# timmy.net
KiCad netlist of a schematic drawn in EAGLE
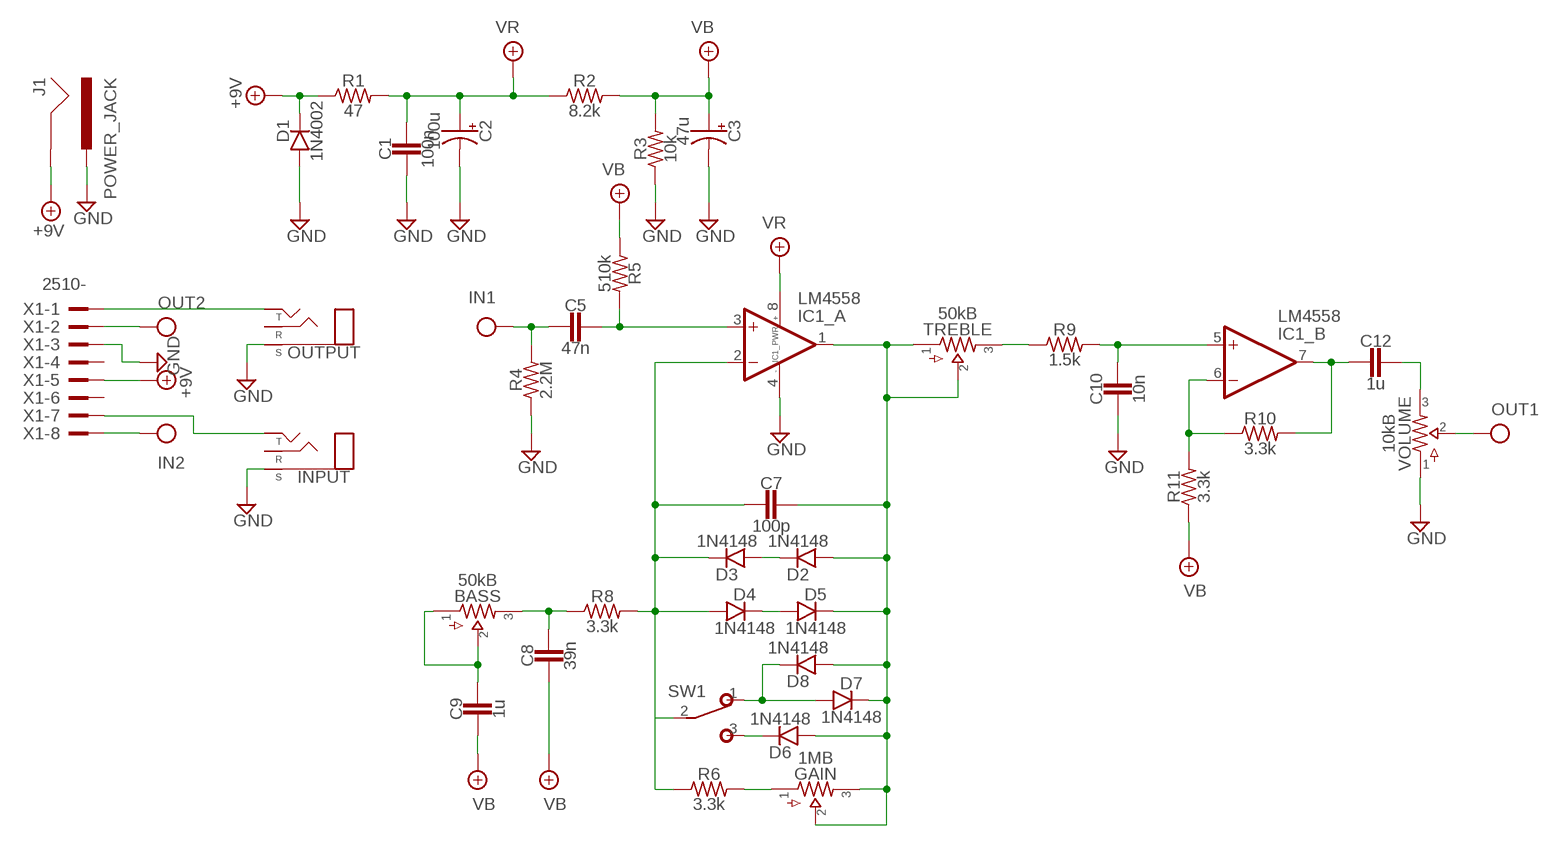
[diagram p0: schematic, sheet 1]

(export (version "E")
  (design (tool "Eeschema 10.0.6"))
  (components
    (comp (ref "BASS")
      (value "50kB")
      (footprint "eagle-import:16MM")
      (libsource (lib "eagle-import") (part "POTS16MM"))
    )
    (comp (ref "C1")
      (value "100n")
      (footprint "eagle-import:050X030_025_2")
      (libsource (lib "eagle-import") (part "CER/FILM2"))
    )
    (comp (ref "C2")
      (value "100u")
      (footprint "eagle-import:050_020")
      (libsource (lib "eagle-import") (part "0500"))
    )
    (comp (ref "C3")
      (value "47u")
      (footprint "eagle-import:050_020")
      (libsource (lib "eagle-import") (part "0500"))
    )
    (comp (ref "C5")
      (value "47n")
      (footprint "eagle-import:BOX_SMALL")
      (libsource (lib "eagle-import") (part "CER/FILMBOX.1"))
    )
    (comp (ref "C7")
      (value "100p")
      (footprint "eagle-import:050X030_025_2")
      (libsource (lib "eagle-import") (part "CER/FILM2"))
    )
    (comp (ref "C8")
      (value "39n")
      (footprint "eagle-import:BOX_SMALL")
      (libsource (lib "eagle-import") (part "CER/FILMBOX.1"))
    )
    (comp (ref "C9")
      (value "1u")
      (footprint "eagle-import:BOX_BIG")
      (libsource (lib "eagle-import") (part "CER/FILMBOX.3"))
    )
    (comp (ref "C10")
      (value "10n")
      (footprint "eagle-import:BOX_SMALL")
      (libsource (lib "eagle-import") (part "CER/FILMBOX.1"))
    )
    (comp (ref "C12")
      (value "1u")
      (footprint "eagle-import:BOX_BIG")
      (libsource (lib "eagle-import") (part "CER/FILMBOX.3"))
    )
    (comp (ref "D1")
      (value "1N4002")
      (footprint "eagle-import:DO41-2")
      (libsource (lib "eagle-import") (part "DO41.2"))
    )
    (comp (ref "D2")
      (value "1N4148")
      (footprint "eagle-import:DO35-2")
      (libsource (lib "eagle-import") (part "DO35.2"))
    )
    (comp (ref "D3")
      (value "1N4148")
      (footprint "eagle-import:DO35-2")
      (libsource (lib "eagle-import") (part "DO35.2"))
    )
    (comp (ref "D4")
      (value "1N4148")
      (footprint "eagle-import:DO35-2")
      (libsource (lib "eagle-import") (part "DO35.2"))
    )
    (comp (ref "D5")
      (value "1N4148")
      (footprint "eagle-import:DO35-2")
      (libsource (lib "eagle-import") (part "DO35.2"))
    )
    (comp (ref "D6")
      (value "1N4148")
      (footprint "eagle-import:DO35-2")
      (libsource (lib "eagle-import") (part "DO35.2"))
    )
    (comp (ref "D7")
      (value "1N4148")
      (footprint "eagle-import:DO35-2")
      (libsource (lib "eagle-import") (part "DO35.2"))
    )
    (comp (ref "D8")
      (value "1N4148")
      (footprint "eagle-import:DO35-2")
      (libsource (lib "eagle-import") (part "DO35.2"))
    )
    (comp (ref "GAIN")
      (value "1MB")
      (footprint "eagle-import:16MM")
      (libsource (lib "eagle-import") (part "POTS16MM"))
    )
    (comp (ref "IC1")
      (value "LM4558")
      (footprint "eagle-import:DIL08")
      (libsource (lib "eagle-import") (part "DUALTH"))
    )
    (comp (ref "INPUT")
      (value "STEREONMJ")
      (footprint "eagle-import:NMJ6HCD2")
      (libsource (lib "eagle-import") (part "STEREONMJ"))
    )
    (comp (ref "J1")
      (value "POWER_JACK")
      (footprint "eagle-import:POWER_JACK_PTH")
      (libsource (lib "eagle-import") (part "POWER_JACK"))
    )
    (comp (ref "OUTPUT")
      (value "STEREONMJ")
      (footprint "eagle-import:NMJ6HCD2")
      (libsource (lib "eagle-import") (part "STEREONMJ"))
    )
    (comp (ref "R1")
      (value "47")
      (footprint "eagle-import:R0207_3")
      (libsource (lib "eagle-import") (part "R_.3B"))
    )
    (comp (ref "R2")
      (value "8.2k")
      (footprint "eagle-import:R0207_3")
      (libsource (lib "eagle-import") (part "R_.3B"))
    )
    (comp (ref "R3")
      (value "10k")
      (footprint "eagle-import:R0207_3")
      (libsource (lib "eagle-import") (part "R_.3B"))
    )
    (comp (ref "R4")
      (value "2.2M")
      (footprint "eagle-import:R0207_3")
      (libsource (lib "eagle-import") (part "R_.3B"))
    )
    (comp (ref "R5")
      (value "510k")
      (footprint "eagle-import:R0207_3")
      (libsource (lib "eagle-import") (part "R_.3B"))
    )
    (comp (ref "R6")
      (value "3.3k")
      (footprint "eagle-import:R0207_3")
      (libsource (lib "eagle-import") (part "R_.3B"))
    )
    (comp (ref "R8")
      (value "3.3k")
      (footprint "eagle-import:R0207_3")
      (libsource (lib "eagle-import") (part "R_.3B"))
    )
    (comp (ref "R9")
      (value "1.5k")
      (footprint "eagle-import:R0207_3")
      (libsource (lib "eagle-import") (part "R_.3B"))
    )
    (comp (ref "R10")
      (value "3.3k")
      (footprint "eagle-import:R0207_3")
      (libsource (lib "eagle-import") (part "R_.3B"))
    )
    (comp (ref "R11")
      (value "3.3k")
      (footprint "eagle-import:R0207_3")
      (libsource (lib "eagle-import") (part "R_.3B"))
    )
    (comp (ref "SW1")
      (value "SPDT")
      (footprint "eagle-import:M9040P")
      (libsource (lib "eagle-import") (part "SPDT"))
    )
    (comp (ref "TREBLE")
      (value "50kB")
      (footprint "eagle-import:16MM")
      (libsource (lib "eagle-import") (part "POTS16MM"))
    )
    (comp (ref "VOLUME")
      (value "10kB")
      (footprint "eagle-import:16MM")
      (libsource (lib "eagle-import") (part "POTS16MM"))
    )
    (comp (ref "X1")
      (value "2510-")
      (footprint "eagle-import:PAK100_2500-10")
      (fields (field (name "MF") "3M") (field (name "MPN") "2510-6002UB"))
      (libsource (lib "eagle-import") (part "2510-"))
    )
  )
  (nets
    (net (code "1") (name "+9V") (class "Default")
      (node (ref "D1") (pin "C") (pinfunction "C_C") (pintype "passive"))
      (node (ref "J1") (pin "GND") (pinfunction "GND_GND") (pintype "bidirectional"))
      (node (ref "R1") (pin "1") (pinfunction "1_1") (pintype "passive"))
      (node (ref "X1") (pin "5") (pinfunction "KL_5") (pintype "passive"))
    )
    (net (code "2") (name "GND") (class "Default")
      (node (ref "C1") (pin "2") (pinfunction "2_2") (pintype "passive"))
      (node (ref "C10") (pin "2") (pinfunction "2_2") (pintype "passive"))
      (node (ref "C2") (pin "-") (pinfunction "-_-") (pintype "passive"))
      (node (ref "C3") (pin "-") (pinfunction "-_-") (pintype "passive"))
      (node (ref "D1") (pin "A") (pinfunction "A_A") (pintype "passive"))
      (node (ref "IC1") (pin "4") (pinfunction "V-_4") (pintype "power_in"))
      (node (ref "INPUT") (pin "S") (pinfunction "S_S") (pintype "passive"))
      (node (ref "J1") (pin "PWR") (pinfunction "PWR_PWR") (pintype "bidirectional"))
      (node (ref "OUTPUT") (pin "S") (pinfunction "S_S") (pintype "passive"))
      (node (ref "R3") (pin "1") (pinfunction "1_1") (pintype "passive"))
      (node (ref "R4") (pin "1") (pinfunction "1_1") (pintype "passive"))
      (node (ref "VOLUME") (pin "1") (pinfunction "1_1") (pintype "passive"))
      (node (ref "X1") (pin "3") (pinfunction "KL_3") (pintype "passive"))
    )
    (net (code "3") (name "IN") (class "Default")
      (node (ref "C5") (pin "2") (pinfunction "2_2") (pintype "passive"))
      (node (ref "R4") (pin "2") (pinfunction "2_2") (pintype "passive"))
      (node (ref "X1") (pin "8") (pinfunction "KL_8") (pintype "passive"))
    )
    (net (code "4") (name "Net-(BASS-Pad1)") (class "Default")
      (node (ref "BASS") (pin "1") (pinfunction "1_1") (pintype "passive"))
      (node (ref "BASS") (pin "2") (pinfunction "2_2") (pintype "passive"))
      (node (ref "C9") (pin "1") (pinfunction "1_1") (pintype "passive"))
    )
    (net (code "5") (name "Net-(BASS-Pad3)") (class "Default")
      (node (ref "BASS") (pin "3") (pinfunction "3_3") (pintype "passive"))
      (node (ref "C8") (pin "1") (pinfunction "1_1") (pintype "passive"))
      (node (ref "R8") (pin "1") (pinfunction "1_1") (pintype "passive"))
    )
    (net (code "6") (name "Net-(C12-Pad1)") (class "Default")
      (node (ref "C12") (pin "1") (pinfunction "1_1") (pintype "passive"))
      (node (ref "VOLUME") (pin "3") (pinfunction "3_3") (pintype "passive"))
    )
    (net (code "7") (name "Net-(D2-PadC)") (class "Default")
      (node (ref "D2") (pin "C") (pinfunction "C_C") (pintype "passive"))
      (node (ref "D3") (pin "A") (pinfunction "A_A") (pintype "passive"))
    )
    (net (code "8") (name "Net-(D4-PadC)") (class "Default")
      (node (ref "D4") (pin "C") (pinfunction "C_C") (pintype "passive"))
      (node (ref "D5") (pin "A") (pinfunction "A_A") (pintype "passive"))
    )
    (net (code "9") (name "Net-(GAIN-Pad1)") (class "Default")
      (node (ref "GAIN") (pin "1") (pinfunction "1_1") (pintype "passive"))
      (node (ref "R6") (pin "2") (pinfunction "2_2") (pintype "passive"))
    )
    (net (code "10") (name "Net-(IC1A-+IN)") (class "Default")
      (node (ref "C5") (pin "1") (pinfunction "1_1") (pintype "passive"))
      (node (ref "IC1") (pin "3") (pinfunction "+IN_3") (pintype "input"))
      (node (ref "R5") (pin "2") (pinfunction "2_2") (pintype "passive"))
    )
    (net (code "11") (name "Net-(IC1A--IN)") (class "Default")
      (node (ref "C7") (pin "2") (pinfunction "2_2") (pintype "passive"))
      (node (ref "D3") (pin "C") (pinfunction "C_C") (pintype "passive"))
      (node (ref "D4") (pin "A") (pinfunction "A_A") (pintype "passive"))
      (node (ref "IC1") (pin "2") (pinfunction "-IN_2") (pintype "input"))
      (node (ref "R6") (pin "1") (pinfunction "1_1") (pintype "passive"))
      (node (ref "R8") (pin "2") (pinfunction "2_2") (pintype "passive"))
      (node (ref "SW1") (pin "2") (pinfunction "P_2") (pintype "passive"))
    )
    (net (code "12") (name "Net-(IC1A-OUT)") (class "Default")
      (node (ref "C7") (pin "1") (pinfunction "1_1") (pintype "passive"))
      (node (ref "D2") (pin "A") (pinfunction "A_A") (pintype "passive"))
      (node (ref "D5") (pin "C") (pinfunction "C_C") (pintype "passive"))
      (node (ref "D6") (pin "A") (pinfunction "A_A") (pintype "passive"))
      (node (ref "D7") (pin "C") (pinfunction "C_C") (pintype "passive"))
      (node (ref "D8") (pin "A") (pinfunction "A_A") (pintype "passive"))
      (node (ref "GAIN") (pin "2") (pinfunction "2_2") (pintype "passive"))
      (node (ref "GAIN") (pin "3") (pinfunction "3_3") (pintype "passive"))
      (node (ref "IC1") (pin "1") (pinfunction "OUT_1") (pintype "output"))
      (node (ref "TREBLE") (pin "1") (pinfunction "1_1") (pintype "passive"))
      (node (ref "TREBLE") (pin "2") (pinfunction "2_2") (pintype "passive"))
    )
    (net (code "13") (name "Net-(IC1B-+IN)") (class "Default")
      (node (ref "C10") (pin "1") (pinfunction "1_1") (pintype "passive"))
      (node (ref "IC1") (pin "5") (pinfunction "+IN_5") (pintype "input"))
      (node (ref "R9") (pin "2") (pinfunction "2_2") (pintype "passive"))
    )
    (net (code "14") (name "Net-(IC1B--IN)") (class "Default")
      (node (ref "IC1") (pin "6") (pinfunction "-IN_6") (pintype "input"))
      (node (ref "R10") (pin "1") (pinfunction "1_1") (pintype "passive"))
      (node (ref "R11") (pin "2") (pinfunction "2_2") (pintype "passive"))
    )
    (net (code "15") (name "Net-(IC1B-OUT)") (class "Default")
      (node (ref "C12") (pin "2") (pinfunction "2_2") (pintype "passive"))
      (node (ref "IC1") (pin "7") (pinfunction "OUT_7") (pintype "output"))
      (node (ref "R10") (pin "2") (pinfunction "2_2") (pintype "passive"))
    )
    (net (code "16") (name "Net-(R9-Pad1)") (class "Default")
      (node (ref "R9") (pin "1") (pinfunction "1_1") (pintype "passive"))
      (node (ref "TREBLE") (pin "3") (pinfunction "3_3") (pintype "passive"))
    )
    (net (code "17") (name "Net-(SW1-O)") (class "Default")
      (node (ref "D7") (pin "A") (pinfunction "A_A") (pintype "passive"))
      (node (ref "D8") (pin "C") (pinfunction "C_C") (pintype "passive"))
      (node (ref "SW1") (pin "1") (pinfunction "O_1") (pintype "passive"))
    )
    (net (code "18") (name "Net-(SW1-S)") (class "Default")
      (node (ref "D6") (pin "C") (pinfunction "C_C") (pintype "passive"))
      (node (ref "SW1") (pin "3") (pinfunction "S_3") (pintype "passive"))
    )
    (net (code "19") (name "Net-(X1A-KL)") (class "Default")
      (node (ref "OUTPUT") (pin "T") (pinfunction "T_T") (pintype "passive"))
      (node (ref "X1") (pin "1") (pinfunction "KL_1") (pintype "passive"))
    )
    (net (code "20") (name "Net-(X1G-KL)") (class "Default")
      (node (ref "INPUT") (pin "T") (pinfunction "T_T") (pintype "passive"))
      (node (ref "X1") (pin "7") (pinfunction "KL_7") (pintype "passive"))
    )
    (net (code "21") (name "OUT") (class "Default")
      (node (ref "VOLUME") (pin "2") (pinfunction "2_2") (pintype "passive"))
      (node (ref "X1") (pin "2") (pinfunction "KL_2") (pintype "passive"))
    )
    (net (code "22") (name "VB") (class "Default")
      (node (ref "C3") (pin "+") (pinfunction "+_+") (pintype "passive"))
      (node (ref "C8") (pin "2") (pinfunction "2_2") (pintype "passive"))
      (node (ref "C9") (pin "2") (pinfunction "2_2") (pintype "passive"))
      (node (ref "R11") (pin "1") (pinfunction "1_1") (pintype "passive"))
      (node (ref "R2") (pin "2") (pinfunction "2_2") (pintype "passive"))
      (node (ref "R3") (pin "2") (pinfunction "2_2") (pintype "passive"))
      (node (ref "R5") (pin "1") (pinfunction "1_1") (pintype "passive"))
    )
    (net (code "23") (name "VR") (class "Default")
      (node (ref "C1") (pin "1") (pinfunction "1_1") (pintype "passive"))
      (node (ref "C2") (pin "+") (pinfunction "+_+") (pintype "passive"))
      (node (ref "IC1") (pin "8") (pinfunction "V+_8") (pintype "power_in"))
      (node (ref "R1") (pin "2") (pinfunction "2_2") (pintype "passive"))
      (node (ref "R2") (pin "1") (pinfunction "1_1") (pintype "passive"))
    )
    (net (code "24") (name "unconnected-(INPUT-PadR)") (class "Default")
      (node (ref "INPUT") (pin "R") (pinfunction "R_R") (pintype "passive"))
    )
    (net (code "25") (name "unconnected-(OUTPUT-PadR)") (class "Default")
      (node (ref "OUTPUT") (pin "R") (pinfunction "R_R") (pintype "passive"))
    )
    (net (code "26") (name "unconnected-(X1D-KL-Pad4)") (class "Default")
      (node (ref "X1") (pin "4") (pinfunction "KL_4") (pintype "passive"))
    )
    (net (code "27") (name "unconnected-(X1F-KL-Pad6)") (class "Default")
      (node (ref "X1") (pin "6") (pinfunction "KL_6") (pintype "passive"))
    )
  )
)
